# atto-touch.net
KiCad netlist of a schematic drawn in EAGLE
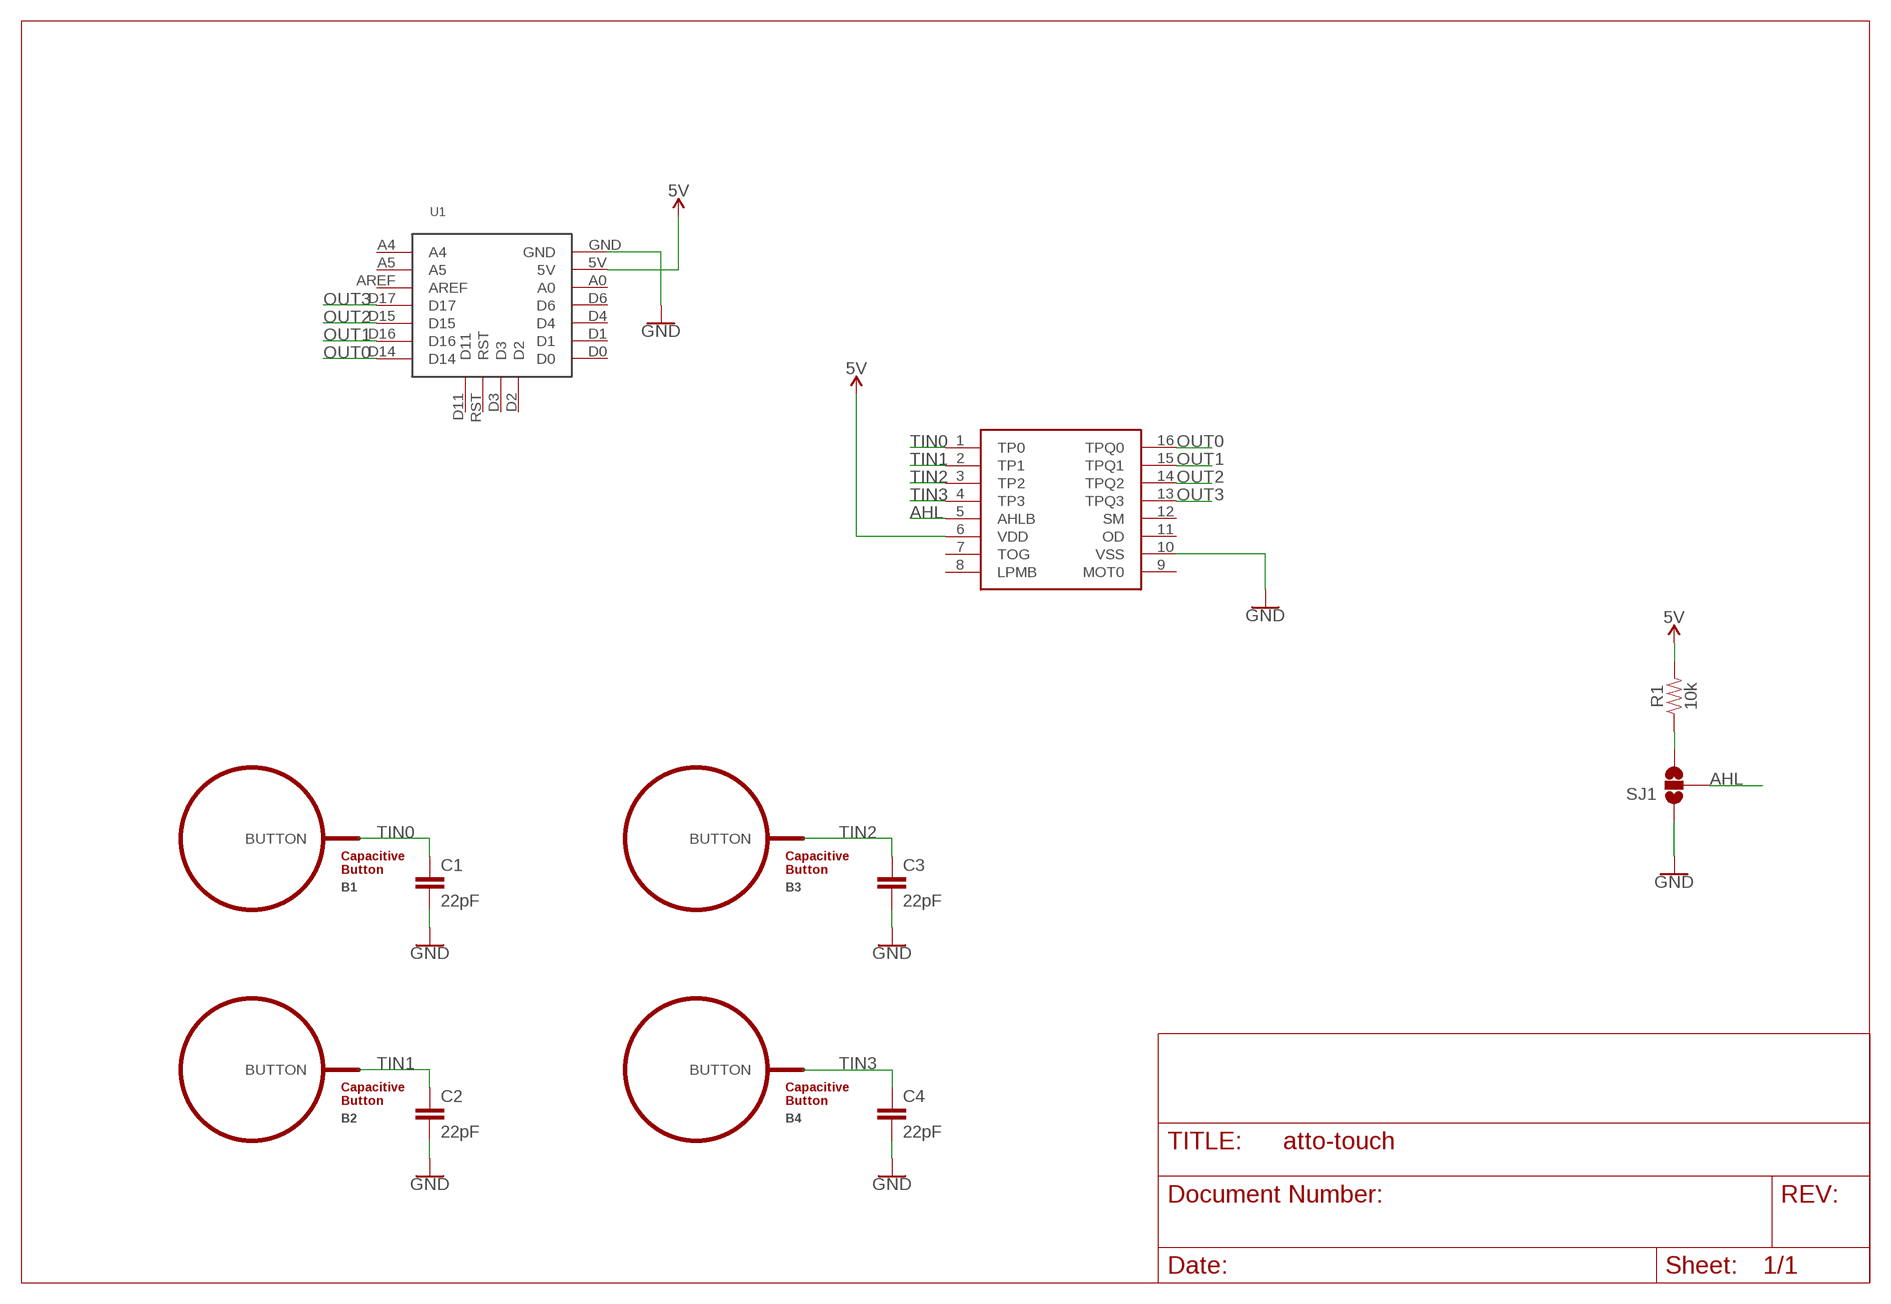
[diagram p0: schematic, sheet 1]

(export (version "E")
  (design (tool "Eeschema 10.0.6"))
  (components
    (comp (ref "B1")
      (value "BUTTON_PASSIVE10MM")
      (footprint "eagle-import:BUTTON_PASSIVE_10MM")
      (libsource (lib "eagle-import") (part "BUTTON_PASSIVE10MM"))
    )
    (comp (ref "B2")
      (value "BUTTON_PASSIVE10MM")
      (footprint "eagle-import:BUTTON_PASSIVE_10MM")
      (libsource (lib "eagle-import") (part "BUTTON_PASSIVE10MM"))
    )
    (comp (ref "B3")
      (value "BUTTON_PASSIVE10MM")
      (footprint "eagle-import:BUTTON_PASSIVE_10MM")
      (libsource (lib "eagle-import") (part "BUTTON_PASSIVE10MM"))
    )
    (comp (ref "B4")
      (value "BUTTON_PASSIVE10MM")
      (footprint "eagle-import:BUTTON_PASSIVE_10MM")
      (libsource (lib "eagle-import") (part "BUTTON_PASSIVE10MM"))
    )
    (comp (ref "C1")
      (value "22pF")
      (footprint "eagle-import:0603")
      (libsource (lib "eagle-import") (part "22PF-0603-50V-5%"))
    )
    (comp (ref "C2")
      (value "22pF")
      (footprint "eagle-import:0603")
      (libsource (lib "eagle-import") (part "22PF-0603-50V-5%"))
    )
    (comp (ref "C3")
      (value "22pF")
      (footprint "eagle-import:0603")
      (libsource (lib "eagle-import") (part "22PF-0603-50V-5%"))
    )
    (comp (ref "C4")
      (value "22pF")
      (footprint "eagle-import:0603")
      (libsource (lib "eagle-import") (part "22PF-0603-50V-5%"))
    )
    (comp (ref "R1")
      (value "10k")
      (footprint "eagle-import:0603")
      (libsource (lib "eagle-import") (part "10KOHM-0603-1/10W-1%"))
    )
    (comp (ref "SJ1")
      (value "SOLDERJUMPER_2WAYS")
      (footprint "eagle-import:SJ_3")
      (libsource (lib "eagle-import") (part "SOLDERJUMPER_2WAYS"))
    )
    (comp (ref "U1")
      (value "PIKSEY_ATTO")
      (footprint "eagle-import:PIKSEY_ATTO")
      (libsource (lib "eagle-import") (part "PIKSEY_ATTO"))
    )
    (comp (ref "U2")
      (value "TTP224")
      (footprint "eagle-import:SSOP-16")
      (libsource (lib "eagle-import") (part "TTP224"))
    )
  )
  (nets
    (net (code "1") (name "/AHL") (class "Default")
      (node (ref "SJ1") (pin "2") (pinfunction "2_2") (pintype "passive"))
      (node (ref "U2") (pin "5") (pinfunction "AHLB_5") (pintype "bidirectional"))
    )
    (net (code "2") (name "/OUT0") (class "Default")
      (node (ref "U1") (pin "D14") (pinfunction "D14_D14") (pintype "bidirectional"))
      (node (ref "U2") (pin "16") (pinfunction "TPQ0_16") (pintype "bidirectional"))
    )
    (net (code "3") (name "/OUT1") (class "Default")
      (node (ref "U1") (pin "D16") (pinfunction "D16_D16") (pintype "bidirectional"))
      (node (ref "U2") (pin "15") (pinfunction "TPQ1_15") (pintype "bidirectional"))
    )
    (net (code "4") (name "/OUT2") (class "Default")
      (node (ref "U1") (pin "D15") (pinfunction "D15_D15") (pintype "bidirectional"))
      (node (ref "U2") (pin "14") (pinfunction "TPQ2_14") (pintype "bidirectional"))
    )
    (net (code "5") (name "/OUT3") (class "Default")
      (node (ref "U1") (pin "D17") (pinfunction "D17_D17") (pintype "bidirectional"))
      (node (ref "U2") (pin "13") (pinfunction "TPQ3_13") (pintype "bidirectional"))
    )
    (net (code "6") (name "/TIN0") (class "Default")
      (node (ref "B1") (pin "BUTTON") (pinfunction "BUTTON_BUTTON") (pintype "passive"))
      (node (ref "C1") (pin "1") (pinfunction "1_1") (pintype "passive"))
      (node (ref "U2") (pin "1") (pinfunction "TP0_1") (pintype "bidirectional"))
    )
    (net (code "7") (name "/TIN1") (class "Default")
      (node (ref "B2") (pin "BUTTON") (pinfunction "BUTTON_BUTTON") (pintype "passive"))
      (node (ref "C2") (pin "1") (pinfunction "1_1") (pintype "passive"))
      (node (ref "U2") (pin "2") (pinfunction "TP1_2") (pintype "bidirectional"))
    )
    (net (code "8") (name "/TIN2") (class "Default")
      (node (ref "B3") (pin "BUTTON") (pinfunction "BUTTON_BUTTON") (pintype "passive"))
      (node (ref "C3") (pin "1") (pinfunction "1_1") (pintype "passive"))
      (node (ref "U2") (pin "3") (pinfunction "TP2_3") (pintype "bidirectional"))
    )
    (net (code "9") (name "/TIN3") (class "Default")
      (node (ref "B4") (pin "BUTTON") (pinfunction "BUTTON_BUTTON") (pintype "passive"))
      (node (ref "C4") (pin "1") (pinfunction "1_1") (pintype "passive"))
      (node (ref "U2") (pin "4") (pinfunction "TP3_4") (pintype "bidirectional"))
    )
    (net (code "10") (name "5V") (class "Default")
      (node (ref "R1") (pin "2") (pinfunction "2_2") (pintype "passive"))
      (node (ref "U1") (pin "5V") (pinfunction "5V_5V") (pintype "bidirectional"))
      (node (ref "U2") (pin "6") (pinfunction "VDD_6") (pintype "bidirectional"))
    )
    (net (code "11") (name "GND") (class "Default")
      (node (ref "C1") (pin "2") (pinfunction "2_2") (pintype "passive"))
      (node (ref "C2") (pin "2") (pinfunction "2_2") (pintype "passive"))
      (node (ref "C3") (pin "2") (pinfunction "2_2") (pintype "passive"))
      (node (ref "C4") (pin "2") (pinfunction "2_2") (pintype "passive"))
      (node (ref "SJ1") (pin "1") (pinfunction "1_1") (pintype "passive"))
      (node (ref "U1") (pin "GND") (pinfunction "GND_GND") (pintype "bidirectional"))
      (node (ref "U2") (pin "10") (pinfunction "VSS_10") (pintype "bidirectional"))
    )
    (net (code "12") (name "Net-(R1-Pad1)") (class "Default")
      (node (ref "R1") (pin "1") (pinfunction "1_1") (pintype "passive"))
      (node (ref "SJ1") (pin "3") (pinfunction "3_3") (pintype "passive"))
    )
    (net (code "13") (name "unconnected-(U1-PadA0)") (class "Default")
      (node (ref "U1") (pin "A0") (pinfunction "A0_A0") (pintype "bidirectional"))
    )
    (net (code "14") (name "unconnected-(U1-PadA4)") (class "Default")
      (node (ref "U1") (pin "A4") (pinfunction "A4_A4") (pintype "bidirectional"))
    )
    (net (code "15") (name "unconnected-(U1-PadA5)") (class "Default")
      (node (ref "U1") (pin "A5") (pinfunction "A5_A5") (pintype "bidirectional"))
    )
    (net (code "16") (name "unconnected-(U1-PadAREF)") (class "Default")
      (node (ref "U1") (pin "AREF") (pinfunction "AREF_AREF") (pintype "bidirectional"))
    )
    (net (code "17") (name "unconnected-(U1-PadD0)") (class "Default")
      (node (ref "U1") (pin "D0") (pinfunction "D0_D0") (pintype "bidirectional"))
    )
    (net (code "18") (name "unconnected-(U1-PadD1)") (class "Default")
      (node (ref "U1") (pin "D1") (pinfunction "D1_D1") (pintype "bidirectional"))
    )
    (net (code "19") (name "unconnected-(U1-PadD2)") (class "Default")
      (node (ref "U1") (pin "D2") (pinfunction "D2_D2") (pintype "bidirectional"))
    )
    (net (code "20") (name "unconnected-(U1-PadD3)") (class "Default")
      (node (ref "U1") (pin "D3") (pinfunction "D3_D3") (pintype "bidirectional"))
    )
    (net (code "21") (name "unconnected-(U1-PadD4)") (class "Default")
      (node (ref "U1") (pin "D4") (pinfunction "D4_D4") (pintype "bidirectional"))
    )
    (net (code "22") (name "unconnected-(U1-PadD6)") (class "Default")
      (node (ref "U1") (pin "D6") (pinfunction "D6_D6") (pintype "bidirectional"))
    )
    (net (code "23") (name "unconnected-(U1-PadD11)") (class "Default")
      (node (ref "U1") (pin "D11") (pinfunction "D11_D11") (pintype "bidirectional"))
    )
    (net (code "24") (name "unconnected-(U1-PadRST)") (class "Default")
      (node (ref "U1") (pin "RST") (pinfunction "RST_RST") (pintype "bidirectional"))
    )
    (net (code "25") (name "unconnected-(U2-LPMB-Pad8)") (class "Default")
      (node (ref "U2") (pin "8") (pinfunction "LPMB_8") (pintype "bidirectional"))
    )
    (net (code "26") (name "unconnected-(U2-MOT0-Pad9)") (class "Default")
      (node (ref "U2") (pin "9") (pinfunction "MOT0_9") (pintype "bidirectional"))
    )
    (net (code "27") (name "unconnected-(U2-OD-Pad11)") (class "Default")
      (node (ref "U2") (pin "11") (pinfunction "OD_11") (pintype "bidirectional"))
    )
    (net (code "28") (name "unconnected-(U2-SM-Pad12)") (class "Default")
      (node (ref "U2") (pin "12") (pinfunction "SM_12") (pintype "bidirectional"))
    )
    (net (code "29") (name "unconnected-(U2-TOG-Pad7)") (class "Default")
      (node (ref "U2") (pin "7") (pinfunction "TOG_7") (pintype "bidirectional"))
    )
  )
)
